# power_protection_board.net
KiCad netlist of a schematic drawn in Altium Designer
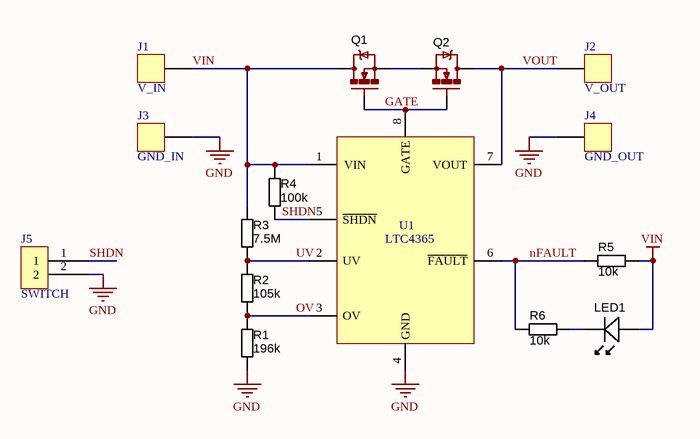
[diagram p0: power_protection_board.SchDoc]

(export (version "E")
  (design (tool "Eeschema 10.0.6"))
  (components
    (comp (ref "J1") (value "V_IN") (footprint "POWER-PAD") (libsource (lib "") (part "HEADER-1_1")))
    (comp (ref "J2") (value "V_OUT") (footprint "POWER-PAD") (libsource (lib "connectors") (part "HEADER-1")))
    (comp (ref "J3") (value "GND_IN") (footprint "POWER-PAD") (libsource (lib "") (part "HEADER-1_1")))
    (comp (ref "J4")
      (value "GND_OUT")
      (footprint "POWER-PAD")
      (libsource (lib "connectors") (part "HEADER-1"))
    )
    (comp (ref "J5")
      (value "SWITCH")
      (footprint "PADS-2-1020")
      (libsource (lib "connectors") (part "HEADER-2"))
    )
    (comp (ref "LED1")
      (value "~")
      (footprint "LED-0603-GREEN")
      (description "LED 0603 SMD Green 525nm 350mcd 20mA")
      (libsource (lib "PBL - Light Sources") (part "LED_SMD_Green_0603_525nm_350mcd"))
    )
    (comp (ref "Q1") (value "MOSFET-N") (footprint "SOT669") (libsource (lib "") (part "MOSFET-N_1")))
    (comp (ref "Q2") (value "MOSFET-N") (footprint "SOT669") (libsource (lib "mosfets") (part "MOSFET-N")))
    (comp (ref "R1")
      (value "196k")
      (footprint "RESC1608X55N")
      (description "Resistor SMD chip 1.5k Ohm 0.1W 5% 0603")
      (fields (field (name "TOLERANCE") "±5%"))
      (libsource (lib "") (part "RES_1K5_0603_5%_1"))
    )
    (comp (ref "R2")
      (value "105k")
      (footprint "RESC1608X55N")
      (description "Resistor SMD chip 1.5k Ohm 0.1W 5% 0603")
      (fields (field (name "TOLERANCE") "±5%"))
      (libsource (lib "") (part "RES_1K5_0603_5%_1"))
    )
    (comp (ref "R3")
      (value "7.5M")
      (footprint "RESC1608X55N")
      (description "Resistor SMD chip 1.5k Ohm 0.1W 5% 0603")
      (fields (field (name "TOLERANCE") "±5%"))
      (libsource (lib "") (part "RES_1K5_0603_5%_1"))
    )
    (comp (ref "R4")
      (value "100k")
      (footprint "RESC1608X55N")
      (description "Resistor SMD chip 1.5k Ohm 0.1W 5% 0603")
      (fields (field (name "TOLERANCE") "±5%"))
      (libsource (lib "") (part "RES_1K5_0603_5%_1"))
    )
    (comp (ref "R5")
      (value "10k")
      (footprint "RESC1608X55N")
      (description "Resistor SMD chip 1.5k Ohm 0.1W 5% 0603")
      (fields (field (name "TOLERANCE") "±5%"))
      (libsource (lib "PBL - Resistors") (part "RES_1K5_0603_5%"))
    )
    (comp (ref "R6")
      (value "10k")
      (footprint "RESC1608X55N")
      (description "Resistor SMD chip 1.5k Ohm 0.1W 5% 0603")
      (fields (field (name "TOLERANCE") "±5%"))
      (libsource (lib "PBL - Resistors") (part "RES_1K5_0603_5%"))
    )
    (comp (ref "U1") (value "LTC4365") (footprint "SOT23-8") (libsource (lib "power") (part "LTC4365")))
  )
  (nets
    (net (code "1") (name "/GATE") (class "Default")
      (node (ref "Q1") (pin "G") (pinfunction "G_G") (pintype "passive"))
      (node (ref "Q2") (pin "G") (pinfunction "G_G") (pintype "passive"))
      (node (ref "U1") (pin "8") (pinfunction "GATE_8") (pintype "passive"))
    )
    (net (code "2") (name "/OV") (class "Default")
      (node (ref "R1") (pin "2") (pinfunction "2_2") (pintype "passive"))
      (node (ref "R2") (pin "1") (pinfunction "1_1") (pintype "passive"))
      (node (ref "U1") (pin "3") (pinfunction "OV_3") (pintype "passive"))
    )
    (net (code "3") (name "/SHDN") (class "Default")
      (node (ref "J5") (pin "1") (pinfunction "1_1") (pintype "passive"))
      (node (ref "R4") (pin "1") (pinfunction "1_1") (pintype "passive"))
      (node (ref "U1") (pin "5") (pinfunction "~{SHDN}_5") (pintype "passive"))
    )
    (net (code "4") (name "/UV") (class "Default")
      (node (ref "R2") (pin "2") (pinfunction "2_2") (pintype "passive"))
      (node (ref "R3") (pin "1") (pinfunction "1_1") (pintype "passive"))
      (node (ref "U1") (pin "2") (pinfunction "UV_2") (pintype "passive"))
    )
    (net (code "5") (name "/VOUT") (class "Default")
      (node (ref "J2") (pin "1") (pinfunction "1_1") (pintype "passive"))
      (node (ref "Q2") (pin "D") (pinfunction "D_D") (pintype "passive"))
      (node (ref "U1") (pin "7") (pinfunction "VOUT_7") (pintype "passive"))
    )
    (net (code "6") (name "/nFAULT") (class "Default")
      (node (ref "R5") (pin "1") (pinfunction "1_1") (pintype "passive"))
      (node (ref "R6") (pin "1") (pinfunction "1_1") (pintype "passive"))
      (node (ref "U1") (pin "6") (pinfunction "~{FAULT}_6") (pintype "passive"))
    )
    (net (code "7") (name "GND") (class "Default")
      (node (ref "J3") (pin "1") (pinfunction "1_1") (pintype "passive"))
      (node (ref "J4") (pin "1") (pinfunction "1_1") (pintype "passive"))
      (node (ref "J5") (pin "2") (pinfunction "2_2") (pintype "passive"))
      (node (ref "R1") (pin "1") (pinfunction "1_1") (pintype "passive"))
      (node (ref "U1") (pin "4") (pinfunction "GND_4") (pintype "passive"))
    )
    (net (code "8") (name "Net-(LED1-PadK)") (class "Default")
      (node (ref "LED1") (pin "K") (pinfunction "K_K") (pintype "passive"))
      (node (ref "R6") (pin "2") (pinfunction "2_2") (pintype "passive"))
    )
    (net (code "9") (name "Net-(Q1-PadS)") (class "Default")
      (node (ref "Q1") (pin "S") (pinfunction "S_S") (pintype "passive"))
      (node (ref "Q2") (pin "S") (pinfunction "S_S") (pintype "passive"))
    )
    (net (code "10") (name "VIN") (class "Default")
      (node (ref "J1") (pin "1") (pinfunction "1_1") (pintype "passive"))
      (node (ref "LED1") (pin "A") (pinfunction "A_A") (pintype "passive"))
      (node (ref "Q1") (pin "D") (pinfunction "D_D") (pintype "passive"))
      (node (ref "R3") (pin "2") (pinfunction "2_2") (pintype "passive"))
      (node (ref "R4") (pin "2") (pinfunction "2_2") (pintype "passive"))
      (node (ref "R5") (pin "2") (pinfunction "2_2") (pintype "passive"))
      (node (ref "U1") (pin "1") (pinfunction "VIN_1") (pintype "passive"))
    )
  )
)
